# stm32rf_node.net
KiCad netlist of a schematic drawn in EAGLE
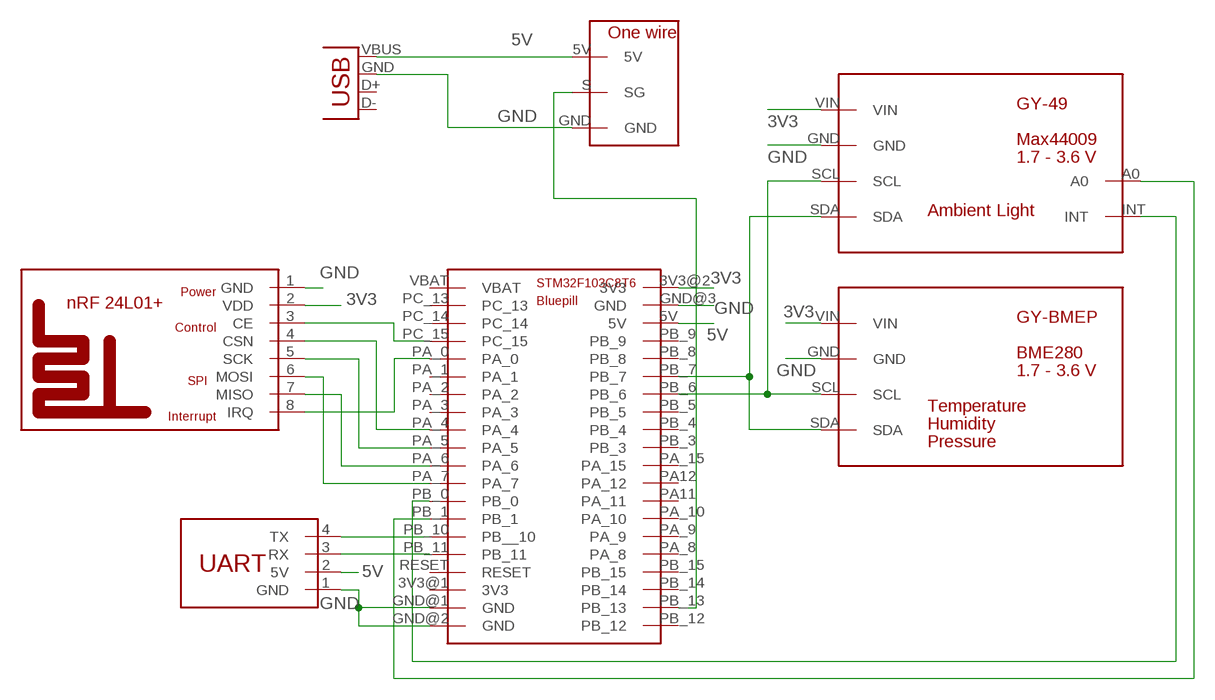
[diagram p0: schematic, sheet 1]

(export (version "E")
  (design (tool "Eeschema 10.0.6"))
  (components
    (comp (ref "U$1")
      (value "STM32_BLUEPILL")
      (footprint "eagle-import:STM32_BLUEPILL")
      (libsource (lib "eagle-import") (part "STM32_BLUEPILL"))
    )
    (comp (ref "U$2")
      (value "NRF24L01+REFDESIGNMINI")
      (footprint "eagle-import:NRF24L01+REFDESIGN-MINI")
      (libsource (lib "eagle-import") (part "NRF24L01+REFDESIGNMINI"))
    )
    (comp (ref "U$3")
      (value "GY-BMEPGY-BMEP-NOHOLE")
      (footprint "eagle-import:GY-BMEP-NOHOLE")
      (libsource (lib "eagle-import") (part "GY-BMEPGY-BMEP-NOHOLE"))
    )
    (comp (ref "U$4")
      (value "GY-49G-49-SURF")
      (footprint "eagle-import:GY-49-SURF")
      (libsource (lib "eagle-import") (part "GY-49G-49-SURF"))
    )
    (comp (ref "U$5")
      (value "ONE_WIRE'RIGHT'")
      (footprint "eagle-import:ONE_WIRE_RIGHT")
      (libsource (lib "eagle-import") (part "ONE_WIRE'RIGHT'"))
    )
    (comp (ref "U$6")
      (value "UARTMINI")
      (footprint "eagle-import:UART-MINI")
      (libsource (lib "eagle-import") (part "UARTMINI"))
    )
    (comp (ref "X1")
      (value "USB-A-H")
      (footprint "eagle-import:USB-A-H")
      (libsource (lib "eagle-import") (part "USB-A-H"))
    )
  )
  (nets
    (net (code "1") (name "/3V3") (class "Default")
      (node (ref "U$1") (pin "3V3@2") (pinfunction "3V3_3V3@2") (pintype "bidirectional"))
      (node (ref "U$2") (pin "2") (pinfunction "VDD_2") (pintype "bidirectional"))
      (node (ref "U$3") (pin "VIN") (pinfunction "VIN_VIN") (pintype "bidirectional"))
      (node (ref "U$4") (pin "VIN") (pinfunction "VIN_VIN") (pintype "bidirectional"))
    )
    (net (code "2") (name "/5V") (class "Default")
      (node (ref "U$1") (pin "5V") (pinfunction "5V_5V") (pintype "bidirectional"))
      (node (ref "U$5") (pin "5V") (pinfunction "5V_5V") (pintype "bidirectional"))
      (node (ref "U$6") (pin "2") (pinfunction "5V_2") (pintype "bidirectional"))
      (node (ref "X1") (pin "VBUS") (pinfunction "GND_VBUS") (pintype "bidirectional"))
    )
    (net (code "3") (name "/GND") (class "Default")
      (node (ref "U$1") (pin "GND@1") (pinfunction "GND_GND@1") (pintype "bidirectional"))
      (node (ref "U$1") (pin "GND@2") (pinfunction "GND_GND@2") (pintype "bidirectional"))
      (node (ref "U$1") (pin "GND@3") (pinfunction "GND_GND@3") (pintype "bidirectional"))
      (node (ref "U$2") (pin "1") (pinfunction "GND_1") (pintype "bidirectional"))
      (node (ref "U$3") (pin "GND") (pinfunction "GND_GND") (pintype "bidirectional"))
      (node (ref "U$4") (pin "GND") (pinfunction "GND_GND") (pintype "bidirectional"))
      (node (ref "U$5") (pin "GND") (pinfunction "GND_GND") (pintype "bidirectional"))
      (node (ref "U$6") (pin "1") (pinfunction "GND_1") (pintype "bidirectional"))
      (node (ref "X1") (pin "GND") (pinfunction "VBUS_GND") (pintype "bidirectional"))
    )
    (net (code "4") (name "Net-(U$1-PB__10)") (class "Default")
      (node (ref "U$1") (pin "PB_10") (pinfunction "PB__10_PB_10") (pintype "bidirectional"))
      (node (ref "U$6") (pin "4") (pinfunction "TX_4") (pintype "bidirectional"))
    )
    (net (code "5") (name "Net-(U$1-PadPB_0)") (class "Default")
      (node (ref "U$1") (pin "PB_0") (pinfunction "PB_0_PB_0") (pintype "bidirectional"))
      (node (ref "U$4") (pin "INT") (pinfunction "INT_INT") (pintype "bidirectional"))
    )
    (net (code "6") (name "Net-(U$1-PadPB_1)") (class "Default")
      (node (ref "U$1") (pin "PB_1") (pinfunction "PB_1_PB_1") (pintype "bidirectional"))
      (node (ref "U$4") (pin "A0") (pinfunction "A0_A0") (pintype "bidirectional"))
    )
    (net (code "7") (name "Net-(U$1-PadPB_6)") (class "Default")
      (node (ref "U$1") (pin "PB_6") (pinfunction "PB_6_PB_6") (pintype "bidirectional"))
      (node (ref "U$3") (pin "SCL") (pinfunction "SCL_SCL") (pintype "bidirectional"))
      (node (ref "U$4") (pin "SCL") (pinfunction "SCL_SCL") (pintype "bidirectional"))
    )
    (net (code "8") (name "Net-(U$1-PadPB_7)") (class "Default")
      (node (ref "U$1") (pin "PB_7") (pinfunction "PB_7_PB_7") (pintype "bidirectional"))
      (node (ref "U$3") (pin "SDA") (pinfunction "SDA_SDA") (pintype "bidirectional"))
      (node (ref "U$4") (pin "SDA") (pinfunction "SDA_SDA") (pintype "bidirectional"))
    )
    (net (code "9") (name "Net-(U$2-CE)") (class "Default")
      (node (ref "U$1") (pin "PC_15") (pinfunction "PC_15_PC_15") (pintype "bidirectional"))
      (node (ref "U$2") (pin "3") (pinfunction "CE_3") (pintype "bidirectional"))
    )
    (net (code "10") (name "Net-(U$2-CSN)") (class "Default")
      (node (ref "U$1") (pin "PA_4") (pinfunction "PA_4_PA_4") (pintype "bidirectional"))
      (node (ref "U$2") (pin "4") (pinfunction "CSN_4") (pintype "bidirectional"))
    )
    (net (code "11") (name "Net-(U$2-IRQ)") (class "Default")
      (node (ref "U$1") (pin "PA_0") (pinfunction "PA_0_PA_0") (pintype "bidirectional"))
      (node (ref "U$2") (pin "8") (pinfunction "IRQ_8") (pintype "bidirectional"))
    )
    (net (code "12") (name "Net-(U$2-MISO)") (class "Default")
      (node (ref "U$1") (pin "PA_6") (pinfunction "PA_6_PA_6") (pintype "bidirectional"))
      (node (ref "U$2") (pin "7") (pinfunction "MISO_7") (pintype "bidirectional"))
    )
    (net (code "13") (name "Net-(U$2-MOSI)") (class "Default")
      (node (ref "U$1") (pin "PA_7") (pinfunction "PA_7_PA_7") (pintype "bidirectional"))
      (node (ref "U$2") (pin "6") (pinfunction "MOSI_6") (pintype "bidirectional"))
    )
    (net (code "14") (name "Net-(U$2-SCK)") (class "Default")
      (node (ref "U$1") (pin "PA_5") (pinfunction "PA_5_PA_5") (pintype "bidirectional"))
      (node (ref "U$2") (pin "5") (pinfunction "SCK_5") (pintype "bidirectional"))
    )
    (net (code "15") (name "Net-(U$5-SG)") (class "Default")
      (node (ref "U$1") (pin "PB_13") (pinfunction "PB_13_PB_13") (pintype "bidirectional"))
      (node (ref "U$5") (pin "S") (pinfunction "SG_S") (pintype "bidirectional"))
    )
    (net (code "16") (name "Net-(U$6-RX)") (class "Default")
      (node (ref "U$1") (pin "PB_11") (pinfunction "PB_11_PB_11") (pintype "bidirectional"))
      (node (ref "U$6") (pin "3") (pinfunction "RX_3") (pintype "bidirectional"))
    )
    (net (code "17") (name "unconnected-(U$1-3V3-Pad3V3@1)") (class "Default")
      (node (ref "U$1") (pin "3V3@1") (pinfunction "3V3_3V3@1") (pintype "bidirectional"))
    )
    (net (code "18") (name "unconnected-(U$1-PA_11-PadPA11)") (class "Default")
      (node (ref "U$1") (pin "PA11") (pinfunction "PA_11_PA11") (pintype "bidirectional"))
    )
    (net (code "19") (name "unconnected-(U$1-PA_12-PadPA12)") (class "Default")
      (node (ref "U$1") (pin "PA12") (pinfunction "PA_12_PA12") (pintype "bidirectional"))
    )
    (net (code "20") (name "unconnected-(U$1-PadPA_1)") (class "Default")
      (node (ref "U$1") (pin "PA_1") (pinfunction "PA_1_PA_1") (pintype "bidirectional"))
    )
    (net (code "21") (name "unconnected-(U$1-PadPA_2)") (class "Default")
      (node (ref "U$1") (pin "PA_2") (pinfunction "PA_2_PA_2") (pintype "bidirectional"))
    )
    (net (code "22") (name "unconnected-(U$1-PadPA_3)") (class "Default")
      (node (ref "U$1") (pin "PA_3") (pinfunction "PA_3_PA_3") (pintype "bidirectional"))
    )
    (net (code "23") (name "unconnected-(U$1-PadPA_8)") (class "Default")
      (node (ref "U$1") (pin "PA_8") (pinfunction "PA_8_PA_8") (pintype "bidirectional"))
    )
    (net (code "24") (name "unconnected-(U$1-PadPA_9)") (class "Default")
      (node (ref "U$1") (pin "PA_9") (pinfunction "PA_9_PA_9") (pintype "bidirectional"))
    )
    (net (code "25") (name "unconnected-(U$1-PadPA_10)") (class "Default")
      (node (ref "U$1") (pin "PA_10") (pinfunction "PA_10_PA_10") (pintype "bidirectional"))
    )
    (net (code "26") (name "unconnected-(U$1-PadPA_15)") (class "Default")
      (node (ref "U$1") (pin "PA_15") (pinfunction "PA_15_PA_15") (pintype "bidirectional"))
    )
    (net (code "27") (name "unconnected-(U$1-PadPB_3)") (class "Default")
      (node (ref "U$1") (pin "PB_3") (pinfunction "PB_3_PB_3") (pintype "bidirectional"))
    )
    (net (code "28") (name "unconnected-(U$1-PadPB_4)") (class "Default")
      (node (ref "U$1") (pin "PB_4") (pinfunction "PB_4_PB_4") (pintype "bidirectional"))
    )
    (net (code "29") (name "unconnected-(U$1-PadPB_5)") (class "Default")
      (node (ref "U$1") (pin "PB_5") (pinfunction "PB_5_PB_5") (pintype "bidirectional"))
    )
    (net (code "30") (name "unconnected-(U$1-PadPB_8)") (class "Default")
      (node (ref "U$1") (pin "PB_8") (pinfunction "PB_8_PB_8") (pintype "bidirectional"))
    )
    (net (code "31") (name "unconnected-(U$1-PadPB_9)") (class "Default")
      (node (ref "U$1") (pin "PB_9") (pinfunction "PB_9_PB_9") (pintype "bidirectional"))
    )
    (net (code "32") (name "unconnected-(U$1-PadPB_12)") (class "Default")
      (node (ref "U$1") (pin "PB_12") (pinfunction "PB_12_PB_12") (pintype "bidirectional"))
    )
    (net (code "33") (name "unconnected-(U$1-PadPB_14)") (class "Default")
      (node (ref "U$1") (pin "PB_14") (pinfunction "PB_14_PB_14") (pintype "bidirectional"))
    )
    (net (code "34") (name "unconnected-(U$1-PadPB_15)") (class "Default")
      (node (ref "U$1") (pin "PB_15") (pinfunction "PB_15_PB_15") (pintype "bidirectional"))
    )
    (net (code "35") (name "unconnected-(U$1-PadPC_13)") (class "Default")
      (node (ref "U$1") (pin "PC_13") (pinfunction "PC_13_PC_13") (pintype "bidirectional"))
    )
    (net (code "36") (name "unconnected-(U$1-PadPC_14)") (class "Default")
      (node (ref "U$1") (pin "PC_14") (pinfunction "PC_14_PC_14") (pintype "bidirectional"))
    )
    (net (code "37") (name "unconnected-(U$1-PadRESET)") (class "Default")
      (node (ref "U$1") (pin "RESET") (pinfunction "RESET_RESET") (pintype "bidirectional"))
    )
    (net (code "38") (name "unconnected-(U$1-PadVBAT)") (class "Default")
      (node (ref "U$1") (pin "VBAT") (pinfunction "VBAT_VBAT") (pintype "bidirectional"))
    )
    (net (code "39") (name "unconnected-(X1-D+-PadD-)") (class "Default")
      (node (ref "X1") (pin "D-") (pinfunction "D+_D-") (pintype "bidirectional"))
    )
    (net (code "40") (name "unconnected-(X1-D--PadD+)") (class "Default")
      (node (ref "X1") (pin "D+") (pinfunction "D-_D+") (pintype "bidirectional"))
    )
  )
)
